# esp8266-board.net
KiCad netlist of a schematic drawn in EAGLE
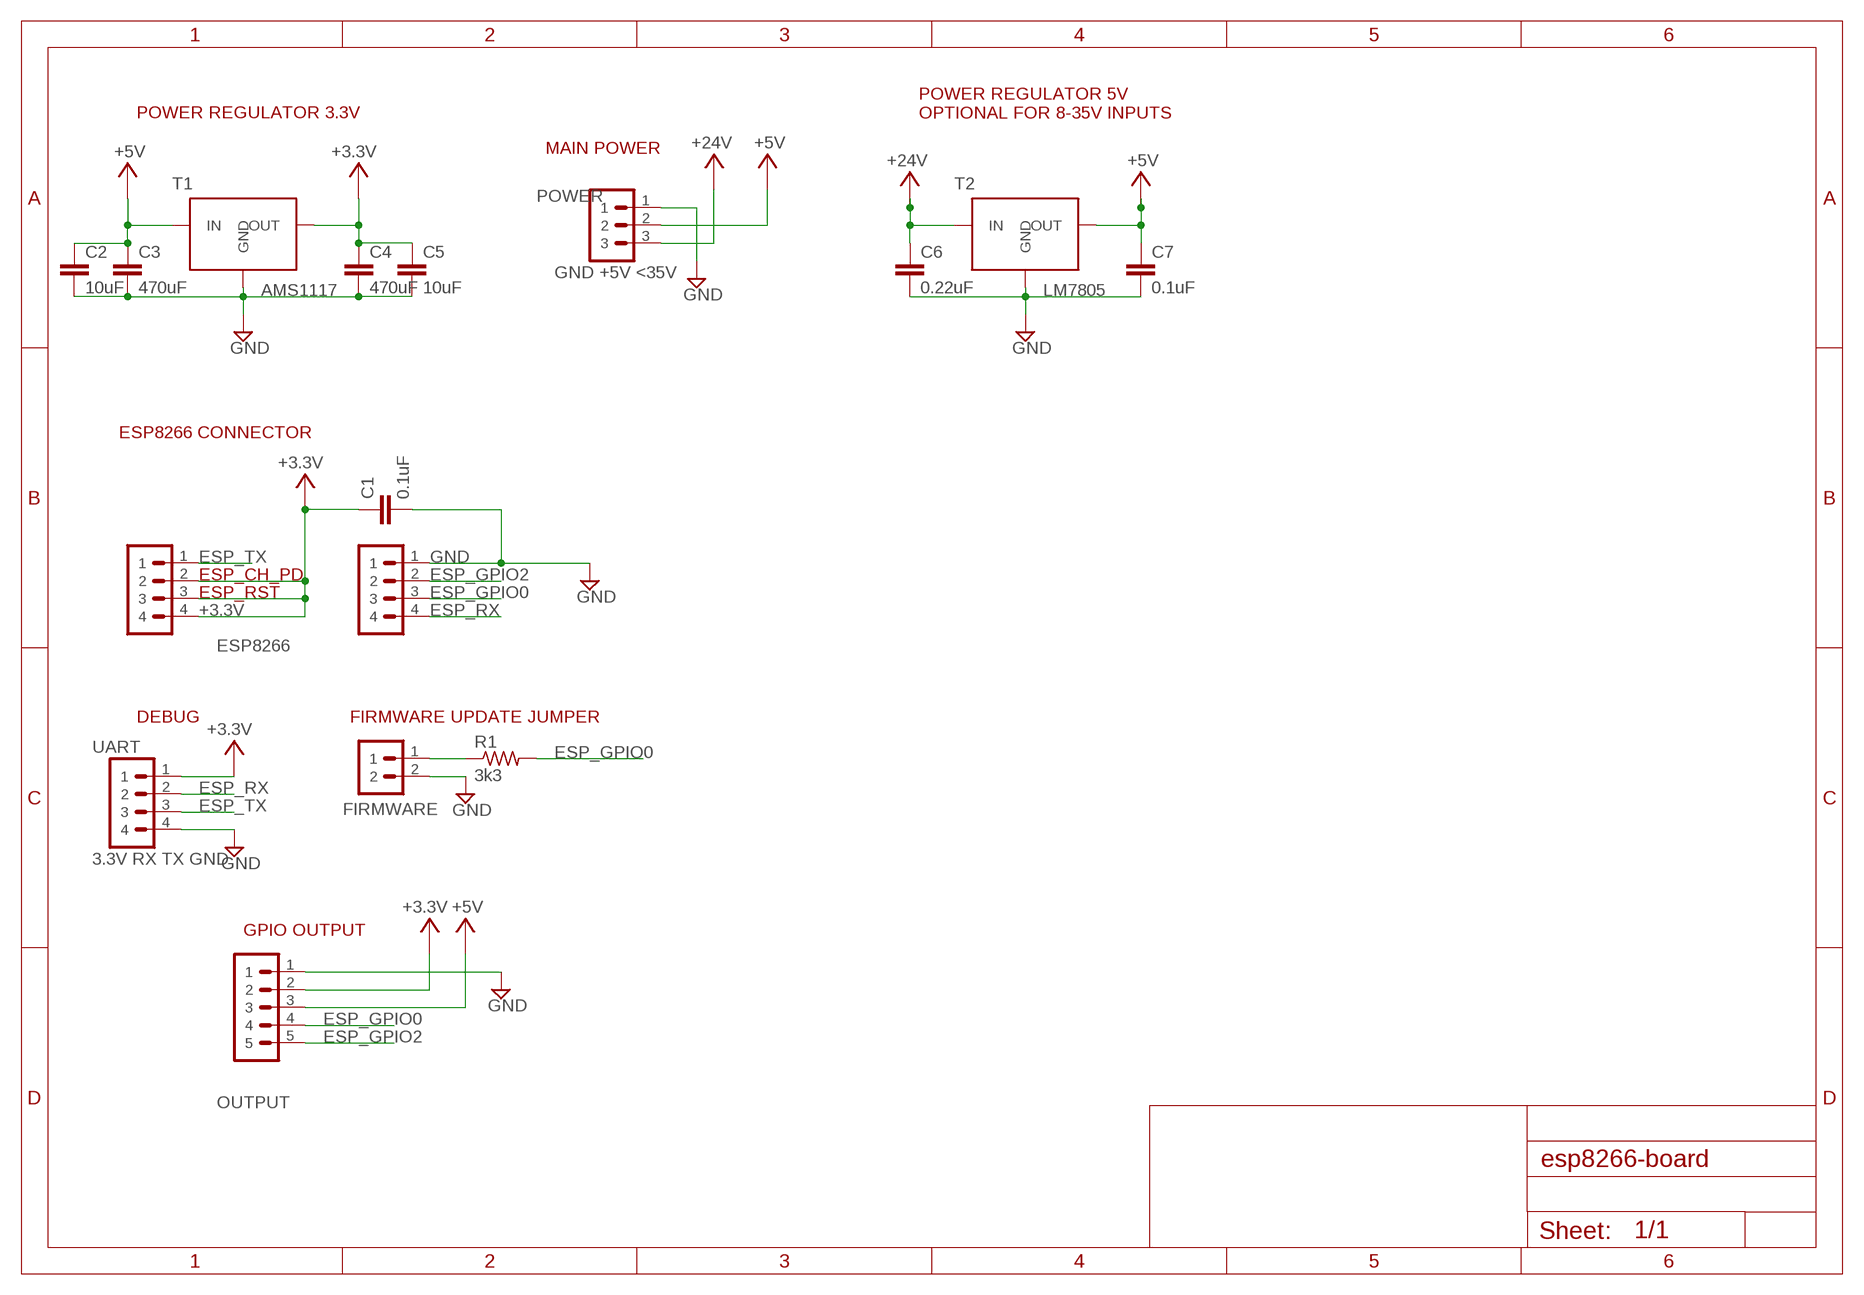
[diagram p0: schematic, sheet 1]

(export (version "E")
  (design (tool "Eeschema 10.0.6"))
  (components
    (comp (ref "C1")
      (value "0.1uF")
      (footprint "eagle-import:C2.5-2")
      (libsource (lib "eagle-import") (part "C2.5/2"))
    )
    (comp (ref "C2")
      (value "10uF")
      (footprint "eagle-import:C2.5-2")
      (libsource (lib "eagle-import") (part "C2.5/2"))
    )
    (comp (ref "C3")
      (value "470uF")
      (footprint "eagle-import:C2.5-2")
      (fields (field (name "MPN") "1C10Z5U104M050B"))
      (libsource (lib "eagle-import") (part "C2.5/2"))
    )
    (comp (ref "C4")
      (value "470uF")
      (footprint "eagle-import:C2.5-2")
      (fields (field (name "MPN") "FK18X5R0J106M"))
      (libsource (lib "eagle-import") (part "C2.5/2"))
    )
    (comp (ref "C5")
      (value "10uF")
      (footprint "eagle-import:C2.5-2")
      (libsource (lib "eagle-import") (part "C2.5/2"))
    )
    (comp (ref "C6")
      (value "0.22uF")
      (footprint "eagle-import:C2.5-2")
      (fields (field (name "MPN") "1C10Z5U104M050B"))
      (libsource (lib "eagle-import") (part "C2.5/2"))
    )
    (comp (ref "C7")
      (value "0.1uF")
      (footprint "eagle-import:C2.5-2")
      (fields (field (name "MPN") "FK18X5R0J106M"))
      (libsource (lib "eagle-import") (part "C2.5/2"))
    )
    (comp (ref "FIRMWARE")
      (value "FIRMWARE")
      (footprint "eagle-import:PIN-HEADER-2PIN")
      (libsource (lib "eagle-import") (part "PIN-HEADER-2PIN"))
    )
    (comp (ref "OUTPUT")
      (value "GND 3.3V 5V IO0 IO2")
      (footprint "eagle-import:PIN-HEADER-5PIN")
      (libsource (lib "eagle-import") (part "PIN-HEADER-5PIN"))
    )
    (comp (ref "P1")
      (value "ESP8266")
      (footprint "eagle-import:PIN-HEADER-4PIN")
      (libsource (lib "eagle-import") (part "PIN-HEADER-4PIN"))
    )
    (comp (ref "P2")
      (value "ESP8266 CONNECTOR")
      (footprint "eagle-import:PIN-HEADER-4PIN")
      (libsource (lib "eagle-import") (part "PIN-HEADER-4PIN"))
    )
    (comp (ref "POWER")
      (value "GND +5V <35V")
      (footprint "eagle-import:PIN-HEADER-3PIN")
      (libsource (lib "eagle-import") (part "PIN-HEADER-3PIN"))
    )
    (comp (ref "R1")
      (value "3k3")
      (footprint "eagle-import:RESISTOR-V2")
      (libsource (lib "eagle-import") (part "RESISTORV2"))
    )
    (comp (ref "T1")
      (value "AMS1117")
      (footprint "eagle-import:SOT-223")
      (fields (field (name "MPN") "LM2937ET-3.3"))
      (libsource (lib "eagle-import") (part "AMS1117"))
    )
    (comp (ref "T2")
      (value "LM7805")
      (footprint "eagle-import:TO-220")
      (fields (field (name "MPN") "LM2937ET-3.3"))
      (libsource (lib "eagle-import") (part "LM7805"))
    )
    (comp (ref "UART")
      (value "3.3V RX TX GND")
      (footprint "eagle-import:PIN-HEADER-4PIN")
      (libsource (lib "eagle-import") (part "PIN-HEADER-4PIN"))
    )
  )
  (nets
    (net (code "1") (name "+3.3V") (class "Default")
      (node (ref "C1") (pin "1") (pinfunction "1_1") (pintype "passive"))
      (node (ref "C4") (pin "1") (pinfunction "1_1") (pintype "passive"))
      (node (ref "C5") (pin "1") (pinfunction "1_1") (pintype "passive"))
      (node (ref "OUTPUT") (pin "2") (pinfunction "2_2") (pintype "passive"))
      (node (ref "P1") (pin "2") (pinfunction "2_2") (pintype "passive"))
      (node (ref "P1") (pin "3") (pinfunction "3_3") (pintype "passive"))
      (node (ref "P1") (pin "4") (pinfunction "4_4") (pintype "passive"))
      (node (ref "T1") (pin "2") (pinfunction "OUT_2") (pintype "power_in"))
      (node (ref "UART") (pin "1") (pinfunction "1_1") (pintype "passive"))
    )
    (net (code "2") (name "+5V") (class "Default")
      (node (ref "C2") (pin "1") (pinfunction "1_1") (pintype "passive"))
      (node (ref "C3") (pin "1") (pinfunction "1_1") (pintype "passive"))
      (node (ref "C7") (pin "1") (pinfunction "1_1") (pintype "passive"))
      (node (ref "OUTPUT") (pin "3") (pinfunction "3_3") (pintype "passive"))
      (node (ref "POWER") (pin "2") (pinfunction "2_2") (pintype "passive"))
      (node (ref "T1") (pin "3") (pinfunction "IN_3") (pintype "power_in"))
      (node (ref "T2") (pin "OUTPUT") (pinfunction "OUT_OUTPUT") (pintype "power_in"))
    )
    (net (code "3") (name "+24V") (class "Default")
      (node (ref "C6") (pin "1") (pinfunction "1_1") (pintype "passive"))
      (node (ref "POWER") (pin "3") (pinfunction "3_3") (pintype "passive"))
      (node (ref "T2") (pin "INPUT") (pinfunction "IN_INPUT") (pintype "power_in"))
    )
    (net (code "4") (name "/ESP_GPIO0") (class "Default")
      (node (ref "OUTPUT") (pin "4") (pinfunction "4_4") (pintype "passive"))
      (node (ref "P2") (pin "3") (pinfunction "3_3") (pintype "passive"))
      (node (ref "R1") (pin "2") (pinfunction "2_2") (pintype "passive"))
    )
    (net (code "5") (name "/ESP_GPIO2") (class "Default")
      (node (ref "OUTPUT") (pin "5") (pinfunction "5_5") (pintype "passive"))
      (node (ref "P2") (pin "2") (pinfunction "2_2") (pintype "passive"))
    )
    (net (code "6") (name "/ESP_RX") (class "Default")
      (node (ref "P2") (pin "4") (pinfunction "4_4") (pintype "passive"))
      (node (ref "UART") (pin "2") (pinfunction "2_2") (pintype "passive"))
    )
    (net (code "7") (name "/ESP_TX") (class "Default")
      (node (ref "P1") (pin "1") (pinfunction "1_1") (pintype "passive"))
      (node (ref "UART") (pin "3") (pinfunction "3_3") (pintype "passive"))
    )
    (net (code "8") (name "GND") (class "Default")
      (node (ref "C1") (pin "2") (pinfunction "2_2") (pintype "passive"))
      (node (ref "C2") (pin "2") (pinfunction "2_2") (pintype "passive"))
      (node (ref "C3") (pin "2") (pinfunction "2_2") (pintype "passive"))
      (node (ref "C4") (pin "2") (pinfunction "2_2") (pintype "passive"))
      (node (ref "C5") (pin "2") (pinfunction "2_2") (pintype "passive"))
      (node (ref "C6") (pin "2") (pinfunction "2_2") (pintype "passive"))
      (node (ref "C7") (pin "2") (pinfunction "2_2") (pintype "passive"))
      (node (ref "FIRMWARE") (pin "2") (pinfunction "2_2") (pintype "passive"))
      (node (ref "OUTPUT") (pin "1") (pinfunction "1_1") (pintype "passive"))
      (node (ref "P2") (pin "1") (pinfunction "1_1") (pintype "passive"))
      (node (ref "POWER") (pin "1") (pinfunction "1_1") (pintype "passive"))
      (node (ref "T1") (pin "1") (pinfunction "GND_1") (pintype "power_in"))
      (node (ref "T2") (pin "GND") (pinfunction "GND_GND") (pintype "power_in"))
      (node (ref "UART") (pin "4") (pinfunction "4_4") (pintype "passive"))
    )
    (net (code "9") (name "Net-(FIRMWARE-Pad1)") (class "Default")
      (node (ref "FIRMWARE") (pin "1") (pinfunction "1_1") (pintype "passive"))
      (node (ref "R1") (pin "1") (pinfunction "1_1") (pintype "passive"))
    )
  )
)
